# CompletePCBV5.net
KiCad netlist of a schematic drawn in EAGLE
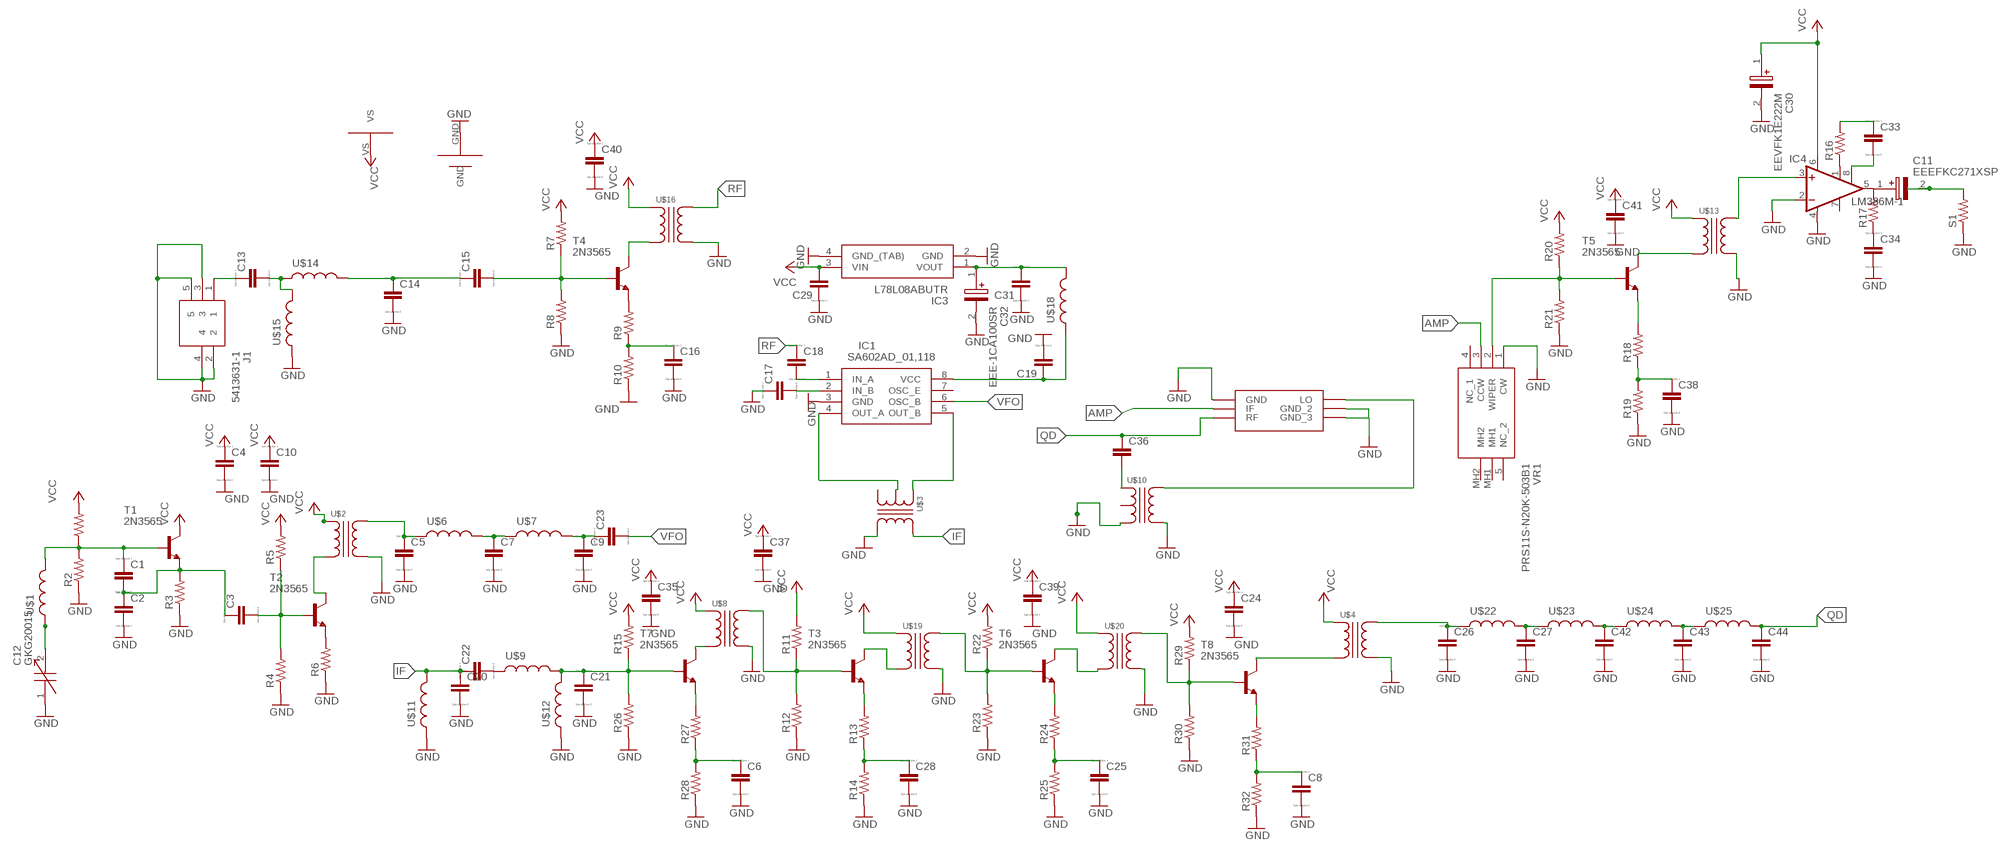
[diagram p0: schematic, sheet 1]

(export (version "E")
  (design (tool "Eeschema 10.0.6"))
  (components
    (comp (ref "C1") (value "C") (footprint "eagle-import:C0805") (libsource (lib "eagle-import") (part "C")))
    (comp (ref "C2") (value "C") (footprint "eagle-import:C0805") (libsource (lib "eagle-import") (part "C")))
    (comp (ref "C3") (value "C") (footprint "eagle-import:C0805") (libsource (lib "eagle-import") (part "C")))
    (comp (ref "C4") (value "C") (footprint "eagle-import:C0805") (libsource (lib "eagle-import") (part "C")))
    (comp (ref "C5") (value "C") (footprint "eagle-import:C0805") (libsource (lib "eagle-import") (part "C")))
    (comp (ref "C6") (value "C") (footprint "eagle-import:C0805") (libsource (lib "eagle-import") (part "C")))
    (comp (ref "C7") (value "C") (footprint "eagle-import:C0805") (libsource (lib "eagle-import") (part "C")))
    (comp (ref "C8") (value "C") (footprint "eagle-import:C0805") (libsource (lib "eagle-import") (part "C")))
    (comp (ref "C9") (value "C") (footprint "eagle-import:C0805") (libsource (lib "eagle-import") (part "C")))
    (comp (ref "C10")
      (value "C")
      (footprint "eagle-import:C0805")
      (libsource (lib "eagle-import") (part "C"))
    )
    (comp (ref "C11")
      (value "EEEFKC271XSP")
      (footprint "eagle-import:FKSV(D8)")
      (libsource (lib "eagle-import") (part "EEEFKC271XSP"))
    )
    (comp (ref "C12")
      (value "GKG20015")
      (footprint "eagle-import:GKG20015")
      (fields (field (name "MOUSER_PART_NUMBER") "659-GKG20015"))
      (libsource (lib "eagle-import") (part "GKG20015"))
    )
    (comp (ref "C13")
      (value "C")
      (footprint "eagle-import:C0805")
      (libsource (lib "eagle-import") (part "C"))
    )
    (comp (ref "C14")
      (value "C")
      (footprint "eagle-import:C0805")
      (libsource (lib "eagle-import") (part "C"))
    )
    (comp (ref "C15")
      (value "C")
      (footprint "eagle-import:C0805")
      (libsource (lib "eagle-import") (part "C"))
    )
    (comp (ref "C16")
      (value "C")
      (footprint "eagle-import:C0805")
      (libsource (lib "eagle-import") (part "C"))
    )
    (comp (ref "C17")
      (value "C")
      (footprint "eagle-import:C0805")
      (libsource (lib "eagle-import") (part "C"))
    )
    (comp (ref "C18")
      (value "C")
      (footprint "eagle-import:C0805")
      (libsource (lib "eagle-import") (part "C"))
    )
    (comp (ref "C19")
      (value "C")
      (footprint "eagle-import:C0805")
      (libsource (lib "eagle-import") (part "C"))
    )
    (comp (ref "C20")
      (value "C")
      (footprint "eagle-import:C0805")
      (libsource (lib "eagle-import") (part "C"))
    )
    (comp (ref "C21")
      (value "C")
      (footprint "eagle-import:C0805")
      (libsource (lib "eagle-import") (part "C"))
    )
    (comp (ref "C22")
      (value "C")
      (footprint "eagle-import:C0805")
      (libsource (lib "eagle-import") (part "C"))
    )
    (comp (ref "C23")
      (value "C")
      (footprint "eagle-import:C0805")
      (libsource (lib "eagle-import") (part "C"))
    )
    (comp (ref "C24")
      (value "C")
      (footprint "eagle-import:C0805")
      (libsource (lib "eagle-import") (part "C"))
    )
    (comp (ref "C25")
      (value "C")
      (footprint "eagle-import:C0805")
      (libsource (lib "eagle-import") (part "C"))
    )
    (comp (ref "C26")
      (value "C")
      (footprint "eagle-import:C0805")
      (libsource (lib "eagle-import") (part "C"))
    )
    (comp (ref "C27")
      (value "C")
      (footprint "eagle-import:C0805")
      (libsource (lib "eagle-import") (part "C"))
    )
    (comp (ref "C28")
      (value "C")
      (footprint "eagle-import:C0805")
      (libsource (lib "eagle-import") (part "C"))
    )
    (comp (ref "C29")
      (value "C")
      (footprint "eagle-import:C0805")
      (libsource (lib "eagle-import") (part "C"))
    )
    (comp (ref "C30")
      (value "EEVFK1E222M")
      (footprint "eagle-import:FKV(J16)")
      (libsource (lib "eagle-import") (part "EEVFK1E222M"))
    )
    (comp (ref "C31")
      (value "C")
      (footprint "eagle-import:C0805")
      (libsource (lib "eagle-import") (part "C"))
    )
    (comp (ref "C32")
      (value "EEE-1CA100SR")
      (footprint "eagle-import:SV(B)")
      (fields (field (name "MOUSER_PART_NUMBER") "667-EEE-1CA100SR"))
      (libsource (lib "eagle-import") (part "EEE-1CA100SR"))
    )
    (comp (ref "C33")
      (value "C")
      (footprint "eagle-import:C0805")
      (libsource (lib "eagle-import") (part "C"))
    )
    (comp (ref "C34")
      (value "CC1206")
      (footprint "eagle-import:C1206")
      (libsource (lib "eagle-import") (part "CC1206"))
    )
    (comp (ref "C35")
      (value "C")
      (footprint "eagle-import:C0805")
      (libsource (lib "eagle-import") (part "C"))
    )
    (comp (ref "C36")
      (value "C-EUC0805")
      (footprint "eagle-import:C0805")
      (libsource (lib "eagle-import") (part "C-EUC0805"))
    )
    (comp (ref "C37")
      (value "C")
      (footprint "eagle-import:C0805")
      (libsource (lib "eagle-import") (part "C"))
    )
    (comp (ref "C38")
      (value "C")
      (footprint "eagle-import:C0805")
      (libsource (lib "eagle-import") (part "C"))
    )
    (comp (ref "C39")
      (value "C")
      (footprint "eagle-import:C0805")
      (libsource (lib "eagle-import") (part "C"))
    )
    (comp (ref "C40")
      (value "C")
      (footprint "eagle-import:C0805")
      (libsource (lib "eagle-import") (part "C"))
    )
    (comp (ref "C41")
      (value "C")
      (footprint "eagle-import:C0805")
      (libsource (lib "eagle-import") (part "C"))
    )
    (comp (ref "C42")
      (value "C")
      (footprint "eagle-import:C0805")
      (libsource (lib "eagle-import") (part "C"))
    )
    (comp (ref "C43")
      (value "C")
      (footprint "eagle-import:C0805")
      (libsource (lib "eagle-import") (part "C"))
    )
    (comp (ref "C44")
      (value "C")
      (footprint "eagle-import:C0805")
      (libsource (lib "eagle-import") (part "C"))
    )
    (comp (ref "IC1")
      (value "SA602AD_01,118")
      (footprint "eagle-import:SOIC127P600X175-8N")
      (fields
        (field (name "MANUFACTURER_PART_NUMBER") "SA602AD/01,118")
        (field (name "MOUSER_PART_NUMBER") "771-SA602AD/01-T")
      )
      (libsource (lib "eagle-import") (part "SA602AD_01,118"))
    )
    (comp (ref "IC3")
      (value "L78L08ABUTR")
      (footprint "eagle-import:ST-SOT-89")
      (fields (field (name "MOUSER_PART_NUMBER") "511-L78L08ABU"))
      (libsource (lib "eagle-import") (part "L78L08ABUTR"))
    )
    (comp (ref "IC4")
      (value "LM386M-1")
      (footprint "eagle-import:SO08")
      (libsource (lib "eagle-import") (part "LM386?-M1"))
    )
    (comp (ref "J1")
      (value "5413631-1")
      (footprint "eagle-import:54136311")
      (fields (field (name "MOUSER_PART_NUMBER") "571-5413631-1"))
      (libsource (lib "eagle-import") (part "5413631-1"))
    )
    (comp (ref "R1")
      (value "R-US_R0805")
      (footprint "eagle-import:R0805")
      (libsource (lib "eagle-import") (part "resistor_348_R-US_R0805"))
    )
    (comp (ref "R2")
      (value "R-US_R0805")
      (footprint "eagle-import:R0805")
      (libsource (lib "eagle-import") (part "resistor_348_R-US_R0805"))
    )
    (comp (ref "R3")
      (value "R-US_R0805")
      (footprint "eagle-import:R0805")
      (libsource (lib "eagle-import") (part "resistor_348_R-US_R0805"))
    )
    (comp (ref "R4")
      (value "R-US_R0805")
      (footprint "eagle-import:R0805")
      (libsource (lib "eagle-import") (part "resistor_348_R-US_R0805"))
    )
    (comp (ref "R5")
      (value "R-US_R0805")
      (footprint "eagle-import:R0805")
      (libsource (lib "eagle-import") (part "resistor_348_R-US_R0805"))
    )
    (comp (ref "R6")
      (value "R-US_R0805")
      (footprint "eagle-import:R0805")
      (libsource (lib "eagle-import") (part "resistor_348_R-US_R0805"))
    )
    (comp (ref "R7")
      (value "R-US_R0805")
      (footprint "eagle-import:R0805")
      (libsource (lib "eagle-import") (part "resistor_348_R-US_R0805"))
    )
    (comp (ref "R8")
      (value "R-US_R0805")
      (footprint "eagle-import:R0805")
      (libsource (lib "eagle-import") (part "resistor_348_R-US_R0805"))
    )
    (comp (ref "R9")
      (value "R-US_R0805")
      (footprint "eagle-import:R0805")
      (libsource (lib "eagle-import") (part "resistor_348_R-US_R0805"))
    )
    (comp (ref "R10")
      (value "R-US_R0805")
      (footprint "eagle-import:R0805")
      (libsource (lib "eagle-import") (part "resistor_348_R-US_R0805"))
    )
    (comp (ref "R11")
      (value "R-US_R0805")
      (footprint "eagle-import:R0805")
      (libsource (lib "eagle-import") (part "resistor_348_R-US_R0805"))
    )
    (comp (ref "R12")
      (value "R-US_R0805")
      (footprint "eagle-import:R0805")
      (libsource (lib "eagle-import") (part "resistor_348_R-US_R0805"))
    )
    (comp (ref "R13")
      (value "R-US_R0805")
      (footprint "eagle-import:R0805")
      (libsource (lib "eagle-import") (part "resistor_348_R-US_R0805"))
    )
    (comp (ref "R14")
      (value "R-US_R0805")
      (footprint "eagle-import:R0805")
      (libsource (lib "eagle-import") (part "resistor_348_R-US_R0805"))
    )
    (comp (ref "R15")
      (value "R-US_R0805")
      (footprint "eagle-import:R0805")
      (libsource (lib "eagle-import") (part "resistor_348_R-US_R0805"))
    )
    (comp (ref "R16")
      (value "R-US_R0805")
      (footprint "eagle-import:R0805")
      (libsource (lib "eagle-import") (part "resistor_348_R-US_R0805"))
    )
    (comp (ref "R17")
      (value "R-US_R0805")
      (footprint "eagle-import:R0805")
      (libsource (lib "eagle-import") (part "resistor_348_R-US_R0805"))
    )
    (comp (ref "R18")
      (value "R-US_R0805")
      (footprint "eagle-import:R0805")
      (libsource (lib "eagle-import") (part "resistor_348_R-US_R0805"))
    )
    (comp (ref "R19")
      (value "R-US_R0805")
      (footprint "eagle-import:R0805")
      (libsource (lib "eagle-import") (part "resistor_348_R-US_R0805"))
    )
    (comp (ref "R20")
      (value "R-US_R0805")
      (footprint "eagle-import:R0805")
      (libsource (lib "eagle-import") (part "resistor_348_R-US_R0805"))
    )
    (comp (ref "R21")
      (value "R-US_R0805")
      (footprint "eagle-import:R0805")
      (libsource (lib "eagle-import") (part "resistor_348_R-US_R0805"))
    )
    (comp (ref "R22")
      (value "R-US_R0805")
      (footprint "eagle-import:R0805")
      (libsource (lib "eagle-import") (part "resistor_348_R-US_R0805"))
    )
    (comp (ref "R23")
      (value "R-US_R0805")
      (footprint "eagle-import:R0805")
      (libsource (lib "eagle-import") (part "resistor_348_R-US_R0805"))
    )
    (comp (ref "R24")
      (value "R-US_R0805")
      (footprint "eagle-import:R0805")
      (libsource (lib "eagle-import") (part "resistor_348_R-US_R0805"))
    )
    (comp (ref "R25")
      (value "R-US_R0805")
      (footprint "eagle-import:R0805")
      (libsource (lib "eagle-import") (part "resistor_348_R-US_R0805"))
    )
    (comp (ref "R26")
      (value "R-US_R0805")
      (footprint "eagle-import:R0805")
      (libsource (lib "eagle-import") (part "resistor_348_R-US_R0805"))
    )
    (comp (ref "R27")
      (value "R-US_R0805")
      (footprint "eagle-import:R0805")
      (libsource (lib "eagle-import") (part "resistor_348_R-US_R0805"))
    )
    (comp (ref "R28")
      (value "R-US_R0805")
      (footprint "eagle-import:R0805")
      (libsource (lib "eagle-import") (part "resistor_348_R-US_R0805"))
    )
    (comp (ref "R29")
      (value "R-US_R0805")
      (footprint "eagle-import:R0805")
      (libsource (lib "eagle-import") (part "resistor_348_R-US_R0805"))
    )
    (comp (ref "R30")
      (value "R-US_R0805")
      (footprint "eagle-import:R0805")
      (libsource (lib "eagle-import") (part "resistor_348_R-US_R0805"))
    )
    (comp (ref "R31")
      (value "R-US_R0805")
      (footprint "eagle-import:R0805")
      (libsource (lib "eagle-import") (part "resistor_348_R-US_R0805"))
    )
    (comp (ref "R32")
      (value "R-US_R0805")
      (footprint "eagle-import:R0805")
      (libsource (lib "eagle-import") (part "resistor_348_R-US_R0805"))
    )
    (comp (ref "S1")
      (value "R-US_0207/5V")
      (footprint "eagle-import:0207_5V")
      (libsource (lib "eagle-import") (part "R-US_0207/5V"))
    )
    (comp (ref "T1")
      (value "2N3565")
      (footprint "eagle-import:TO92")
      (libsource (lib "eagle-import") (part "2N3565"))
    )
    (comp (ref "T2")
      (value "2N3565")
      (footprint "eagle-import:TO92")
      (libsource (lib "eagle-import") (part "2N3565"))
    )
    (comp (ref "T3")
      (value "2N3565")
      (footprint "eagle-import:TO92")
      (libsource (lib "eagle-import") (part "2N3565"))
    )
    (comp (ref "T4")
      (value "2N3565")
      (footprint "eagle-import:TO92")
      (libsource (lib "eagle-import") (part "2N3565"))
    )
    (comp (ref "T5")
      (value "2N3565")
      (footprint "eagle-import:TO92")
      (libsource (lib "eagle-import") (part "2N3565"))
    )
    (comp (ref "T6")
      (value "2N3565")
      (footprint "eagle-import:TO92")
      (libsource (lib "eagle-import") (part "2N3565"))
    )
    (comp (ref "T7")
      (value "2N3565")
      (footprint "eagle-import:TO92")
      (libsource (lib "eagle-import") (part "2N3565"))
    )
    (comp (ref "T8")
      (value "2N3565")
      (footprint "eagle-import:TO92")
      (libsource (lib "eagle-import") (part "2N3565"))
    )
    (comp (ref "U$1")
      (value "WOUNDINDUCTOR")
      (footprint "eagle-import:WOUNDINDUCTOR")
      (libsource (lib "eagle-import") (part "WOUNDINDUCTOR"))
    )
    (comp (ref "U$2")
      (value "RFTRANSFORMER")
      (footprint "eagle-import:RFTRABSFORMER")
      (libsource (lib "eagle-import") (part "RFTRANSFORMER"))
    )
    (comp (ref "U$3")
      (value "42IF123")
      (footprint "eagle-import:42IF123")
      (libsource (lib "eagle-import") (part "42IF123"))
    )
    (comp (ref "U$4")
      (value "RFTRANSFORMER")
      (footprint "eagle-import:RFTRABSFORMER")
      (libsource (lib "eagle-import") (part "RFTRANSFORMER"))
    )
    (comp (ref "U$5")
      (value "ALLIGATORCLIPS")
      (footprint "eagle-import:ALLIGATORCONNECTOR")
      (libsource (lib "eagle-import") (part "ALLIGATORCLIPS"))
    )
    (comp (ref "U$6")
      (value "WOUNDINDUCTOR")
      (footprint "eagle-import:WOUNDINDUCTOR")
      (libsource (lib "eagle-import") (part "WOUNDINDUCTOR"))
    )
    (comp (ref "U$7")
      (value "WOUNDINDUCTOR")
      (footprint "eagle-import:WOUNDINDUCTOR")
      (libsource (lib "eagle-import") (part "WOUNDINDUCTOR"))
    )
    (comp (ref "U$8")
      (value "RFTRANSFORMER")
      (footprint "eagle-import:RFTRABSFORMER")
      (libsource (lib "eagle-import") (part "RFTRANSFORMER"))
    )
    (comp (ref "U$9")
      (value "WOUNDINDUCTOR")
      (footprint "eagle-import:WOUNDINDUCTOR")
      (libsource (lib "eagle-import") (part "WOUNDINDUCTOR"))
    )
    (comp (ref "U$10")
      (value "42IF123")
      (footprint "eagle-import:42IF123")
      (libsource (lib "eagle-import") (part "42IF123"))
    )
    (comp (ref "U$11")
      (value "WOUNDINDUCTOR")
      (footprint "eagle-import:WOUNDINDUCTOR")
      (libsource (lib "eagle-import") (part "WOUNDINDUCTOR"))
    )
    (comp (ref "U$12")
      (value "WOUNDINDUCTOR")
      (footprint "eagle-import:WOUNDINDUCTOR")
      (libsource (lib "eagle-import") (part "WOUNDINDUCTOR"))
    )
    (comp (ref "U$13")
      (value "RFTRANSFORMER")
      (footprint "eagle-import:RFTRABSFORMER")
      (libsource (lib "eagle-import") (part "RFTRANSFORMER"))
    )
    (comp (ref "U$14")
      (value "WOUNDINDUCTOR")
      (footprint "eagle-import:WOUNDINDUCTOR")
      (libsource (lib "eagle-import") (part "WOUNDINDUCTOR"))
    )
    (comp (ref "U$15")
      (value "WOUNDINDUCTOR")
      (footprint "eagle-import:WOUNDINDUCTOR")
      (libsource (lib "eagle-import") (part "WOUNDINDUCTOR"))
    )
    (comp (ref "U$16")
      (value "RFTRANSFORMER")
      (footprint "eagle-import:RFTRABSFORMER")
      (libsource (lib "eagle-import") (part "RFTRANSFORMER"))
    )
    (comp (ref "U$17")
      (value "ADE-1")
      (footprint "eagle-import:ADE-1")
      (libsource (lib "eagle-import") (part "ADE-1"))
    )
    (comp (ref "U$18")
      (value "WOUNDINDUCTOR")
      (footprint "eagle-import:WOUNDINDUCTOR")
      (libsource (lib "eagle-import") (part "WOUNDINDUCTOR"))
    )
    (comp (ref "U$19")
      (value "RFTRANSFORMER")
      (footprint "eagle-import:RFTRABSFORMER")
      (libsource (lib "eagle-import") (part "RFTRANSFORMER"))
    )
    (comp (ref "U$20")
      (value "RFTRANSFORMER")
      (footprint "eagle-import:RFTRABSFORMER")
      (libsource (lib "eagle-import") (part "RFTRANSFORMER"))
    )
    (comp (ref "U$22")
      (value "WOUNDINDUCTOR")
      (footprint "eagle-import:WOUNDINDUCTOR")
      (libsource (lib "eagle-import") (part "WOUNDINDUCTOR"))
    )
    (comp (ref "U$23")
      (value "WOUNDINDUCTOR")
      (footprint "eagle-import:WOUNDINDUCTOR")
      (libsource (lib "eagle-import") (part "WOUNDINDUCTOR"))
    )
    (comp (ref "U$24")
      (value "WOUNDINDUCTOR")
      (footprint "eagle-import:WOUNDINDUCTOR")
      (libsource (lib "eagle-import") (part "WOUNDINDUCTOR"))
    )
    (comp (ref "U$25")
      (value "WOUNDINDUCTOR")
      (footprint "eagle-import:WOUNDINDUCTOR")
      (libsource (lib "eagle-import") (part "WOUNDINDUCTOR"))
    )
    (comp (ref "VR1")
      (value "PRS11S-N20K-503B1")
      (footprint "eagle-import:PRS11SN20K503B1")
      (fields (field (name "MOUSER_PART_NUMBER") "652-PRS11SN20K503B1"))
      (libsource (lib "eagle-import") (part "PRS11S-N20K-503B1"))
    )
  )
  (nets
    (net (code "1") (name "AMP") (class "Default")
      (node (ref "U$17") (pin "IF") (pinfunction "IF_IF") (pintype "bidirectional"))
      (node (ref "VR1") (pin "3") (pinfunction "CCW_3") (pintype "bidirectional"))
    )
    (net (code "2") (name "GND") (class "Default")
      (node (ref "C10") (pin "2") (pinfunction "2_2") (pintype "passive"))
      (node (ref "C12") (pin "1") (pinfunction "1_1") (pintype "bidirectional"))
      (node (ref "C14") (pin "2") (pinfunction "2_2") (pintype "passive"))
      (node (ref "C16") (pin "2") (pinfunction "2_2") (pintype "passive"))
      (node (ref "C17") (pin "1") (pinfunction "1_1") (pintype "passive"))
      (node (ref "C19") (pin "2") (pinfunction "2_2") (pintype "passive"))
      (node (ref "C2") (pin "2") (pinfunction "2_2") (pintype "passive"))
      (node (ref "C20") (pin "2") (pinfunction "2_2") (pintype "passive"))
      (node (ref "C21") (pin "2") (pinfunction "2_2") (pintype "passive"))
      (node (ref "C24") (pin "2") (pinfunction "2_2") (pintype "passive"))
      (node (ref "C25") (pin "2") (pinfunction "2_2") (pintype "passive"))
      (node (ref "C26") (pin "2") (pinfunction "2_2") (pintype "passive"))
      (node (ref "C27") (pin "2") (pinfunction "2_2") (pintype "passive"))
      (node (ref "C28") (pin "2") (pinfunction "2_2") (pintype "passive"))
      (node (ref "C29") (pin "1") (pinfunction "1_1") (pintype "passive"))
      (node (ref "C30") (pin "2") (pinfunction "-_2") (pintype "bidirectional"))
      (node (ref "C31") (pin "1") (pinfunction "1_1") (pintype "passive"))
      (node (ref "C32") (pin "2") (pinfunction "-_2") (pintype "bidirectional"))
      (node (ref "C34") (pin "2") (pinfunction "2_2") (pintype "passive"))
      (node (ref "C35") (pin "2") (pinfunction "2_2") (pintype "passive"))
      (node (ref "C37") (pin "2") (pinfunction "2_2") (pintype "passive"))
      (node (ref "C38") (pin "2") (pinfunction "2_2") (pintype "passive"))
      (node (ref "C39") (pin "2") (pinfunction "2_2") (pintype "passive"))
      (node (ref "C4") (pin "2") (pinfunction "2_2") (pintype "passive"))
      (node (ref "C40") (pin "2") (pinfunction "2_2") (pintype "passive"))
      (node (ref "C41") (pin "2") (pinfunction "2_2") (pintype "passive"))
      (node (ref "C42") (pin "2") (pinfunction "2_2") (pintype "passive"))
      (node (ref "C43") (pin "2") (pinfunction "2_2") (pintype "passive"))
      (node (ref "C44") (pin "2") (pinfunction "2_2") (pintype "passive"))
      (node (ref "C5") (pin "2") (pinfunction "2_2") (pintype "passive"))
      (node (ref "C6") (pin "2") (pinfunction "2_2") (pintype "passive"))
      (node (ref "C7") (pin "2") (pinfunction "2_2") (pintype "passive"))
      (node (ref "C8") (pin "2") (pinfunction "2_2") (pintype "passive"))
      (node (ref "C9") (pin "2") (pinfunction "2_2") (pintype "passive"))
      (node (ref "IC1") (pin "3") (pinfunction "GND_3") (pintype "power_in"))
      (node (ref "IC3") (pin "2") (pinfunction "GND_2") (pintype "power_in"))
      (node (ref "IC3") (pin "4") (pinfunction "GND_(TAB)_4") (pintype "power_in"))
      (node (ref "IC4") (pin "2") (pinfunction "-IN_2") (pintype "input"))
      (node (ref "IC4") (pin "4") (pinfunction "GND_4") (pintype "power_in"))
      (node (ref "J1") (pin "2") (pinfunction "2_2") (pintype "bidirectional"))
      (node (ref "J1") (pin "3") (pinfunction "3_3") (pintype "bidirectional"))
      (node (ref "J1") (pin "4") (pinfunction "4_4") (pintype "bidirectional"))
      (node (ref "J1") (pin "5") (pinfunction "5_5") (pintype "bidirectional"))
      (node (ref "R10") (pin "1") (pinfunction "1_1") (pintype "passive"))
      (node (ref "R12") (pin "1") (pinfunction "1_1") (pintype "passive"))
      (node (ref "R14") (pin "1") (pinfunction "1_1") (pintype "passive"))
      (node (ref "R19") (pin "1") (pinfunction "1_1") (pintype "passive"))
      (node (ref "R2") (pin "1") (pinfunction "1_1") (pintype "passive"))
      (node (ref "R21") (pin "1") (pinfunction "1_1") (pintype "passive"))
      (node (ref "R23") (pin "1") (pinfunction "1_1") (pintype "passive"))
      (node (ref "R25") (pin "1") (pinfunction "1_1") (pintype "passive"))
      (node (ref "R26") (pin "1") (pinfunction "1_1") (pintype "passive"))
      (node (ref "R28") (pin "1") (pinfunction "1_1") (pintype "passive"))
      (node (ref "R3") (pin "1") (pinfunction "1_1") (pintype "passive"))
      (node (ref "R30") (pin "1") (pinfunction "1_1") (pintype "passive"))
      (node (ref "R32") (pin "1") (pinfunction "1_1") (pintype "passive"))
      (node (ref "R4") (pin "1") (pinfunction "1_1") (pintype "passive"))
      (node (ref "R6") (pin "1") (pinfunction "1_1") (pintype "passive"))
      (node (ref "R8") (pin "1") (pinfunction "1_1") (pintype "passive"))
      (node (ref "S1") (pin "1") (pinfunction "1_1") (pintype "passive"))
      (node (ref "U$10") (pin "P$3") (pinfunction "P$2_P$3") (pintype "bidirectional"))
      (node (ref "U$10") (pin "P$4") (pinfunction "P$3_P$4") (pintype "bidirectional"))
      (node (ref "U$11") (pin "1") (pinfunction "1_1") (pintype "bidirectional"))
      (node (ref "U$12") (pin "1") (pinfunction "1_1") (pintype "bidirectional"))
      (node (ref "U$13") (pin "P$4") (pinfunction "P$3_P$4") (pintype "bidirectional"))
      (node (ref "U$15") (pin "1") (pinfunction "1_1") (pintype "bidirectional"))
      (node (ref "U$16") (pin "P$4") (pinfunction "P$3_P$4") (pintype "bidirectional"))
      (node (ref "U$17") (pin "GND") (pinfunction "GND_GND") (pintype "bidirectional"))
      (node (ref "U$17") (pin "GND2") (pinfunction "GND_2_GND2") (pintype "bidirectional"))
      (node (ref "U$17") (pin "GND3") (pinfunction "GND_3_GND3") (pintype "bidirectional"))
      (node (ref "U$19") (pin "P$4") (pinfunction "P$3_P$4") (pintype "bidirectional"))
      (node (ref "U$2") (pin "P$4") (pinfunction "P$3_P$4") (pintype "bidirectional"))
      (node (ref "U$20") (pin "P$4") (pinfunction "P$3_P$4") (pintype "bidirectional"))
      (node (ref "U$3") (pin "P$4") (pinfunction "P$3_P$4") (pintype "bidirectional"))
      (node (ref "U$4") (pin "P$4") (pinfunction "P$3_P$4") (pintype "bidirectional"))
      (node (ref "U$5") (pin "GND") (pinfunction "GND_GND") (pintype "bidirectional"))
      (node (ref "U$8") (pin "P$4") (pinfunction "P$3_P$4") (pintype "bidirectional"))
      (node (ref "VR1") (pin "1") (pinfunction "CW_1") (pintype "bidirectional"))
    )
    (net (code "3") (name "IF") (class "Default")
      (node (ref "C20") (pin "1") (pinfunction "1_1") (pintype "passive"))
      (node (ref "C22") (pin "1") (pinfunction "1_1") (pintype "passive"))
      (node (ref "U$11") (pin "2") (pinfunction "2_2") (pintype "bidirectional"))
      (node (ref "U$3") (pin "P$5") (pinfunction "P$4_P$5") (pintype "bidirectional"))
    )
    (net (code "4") (name "Net-(C6-Pad1)") (class "Default")
      (node (ref "C6") (pin "1") (pinfunction "1_1") (pintype "passive"))
      (node (ref "R27") (pin "1") (pinfunction "1_1") (pintype "passive"))
      (node (ref "R28") (pin "2") (pinfunction "2_2") (pintype "passive"))
    )
    (net (code "5") (name "Net-(C7-Pad1)") (class "Default")
      (node (ref "C7") (pin "1") (pinfunction "1_1") (pintype "passive"))
      (node (ref "U$6") (pin "2") (pinfunction "2_2") (pintype "bidirectional"))
      (node (ref "U$7") (pin "1") (pinfunction "1_1") (pintype "bidirectional"))
    )
    (net (code "6") (name "Net-(C8-Pad1)") (class "Default")
      (node (ref "C8") (pin "1") (pinfunction "1_1") (pintype "passive"))
      (node (ref "R31") (pin "1") (pinfunction "1_1") (pintype "passive"))
      (node (ref "R32") (pin "2") (pinfunction "2_2") (pintype "passive"))
    )
    (net (code "7") (name "Net-(C11-+)") (class "Default")
      (node (ref "C11") (pin "1") (pinfunction "+_1") (pintype "bidirectional"))
      (node (ref "IC4") (pin "5") (pinfunction "OUT_5") (pintype "output"))
      (node (ref "R17") (pin "2") (pinfunction "2_2") (pintype "passive"))
    )
    (net (code "8") (name "Net-(C11--)") (class "Default")
      (node (ref "C11") (pin "2") (pinfunction "-_2") (pintype "bidirectional"))
      (node (ref "S1") (pin "2") (pinfunction "2_2") (pintype "passive"))
    )
    (net (code "9") (name "Net-(C12-Pad2)") (class "Default")
      (node (ref "C12") (pin "2") (pinfunction "2_2") (pintype "bidirectional"))
      (node (ref "U$1") (pin "1") (pinfunction "1_1") (pintype "bidirectional"))
    )
    (net (code "10") (name "Net-(C13-Pad1)") (class "Default")
      (node (ref "C13") (pin "1") (pinfunction "1_1") (pintype "passive"))
      (node (ref "J1") (pin "1") (pinfunction "1_1") (pintype "bidirectional"))
    )
    (net (code "11") (name "Net-(C13-Pad2)") (class "Default")
      (node (ref "C13") (pin "2") (pinfunction "2_2") (pintype "passive"))
      (node (ref "U$14") (pin "1") (pinfunction "1_1") (pintype "bidirectional"))
      (node (ref "U$15") (pin "2") (pinfunction "2_2") (pintype "bidirectional"))
    )
    (net (code "12") (name "Net-(C14-Pad1)") (class "Default")
      (node (ref "C14") (pin "1") (pinfunction "1_1") (pintype "passive"))
      (node (ref "C15") (pin "1") (pinfunction "1_1") (pintype "passive"))
      (node (ref "U$14") (pin "2") (pinfunction "2_2") (pintype "bidirectional"))
    )
    (net (code "13") (name "Net-(C16-Pad1)") (class "Default")
      (node (ref "C16") (pin "1") (pinfunction "1_1") (pintype "passive"))
      (node (ref "R10") (pin "2") (pinfunction "2_2") (pintype "passive"))
      (node (ref "R9") (pin "1") (pinfunction "1_1") (pintype "passive"))
    )
    (net (code "14") (name "Net-(C22-Pad2)") (class "Default")
      (node (ref "C22") (pin "2") (pinfunction "2_2") (pintype "passive"))
      (node (ref "U$9") (pin "1") (pinfunction "1_1") (pintype "bidirectional"))
    )
    (net (code "15") (name "Net-(C23-Pad1)") (class "Default")
      (node (ref "C23") (pin "1") (pinfunction "1_1") (pintype "passive"))
      (node (ref "C9") (pin "1") (pinfunction "1_1") (pintype "passive"))
      (node (ref "U$7") (pin "2") (pinfunction "2_2") (pintype "bidirectional"))
    )
    (net (code "16") (name "Net-(C25-Pad1)") (class "Default")
      (node (ref "C25") (pin "1") (pinfunction "1_1") (pintype "passive"))
      (node (ref "R24") (pin "1") (pinfunction "1_1") (pintype "passive"))
      (node (ref "R25") (pin "2") (pinfunction "2_2") (pintype "passive"))
    )
    (net (code "17") (name "Net-(C27-Pad1)") (class "Default")
      (node (ref "C27") (pin "1") (pinfunction "1_1") (pintype "passive"))
      (node (ref "U$22") (pin "2") (pinfunction "2_2") (pintype "bidirectional"))
      (node (ref "U$23") (pin "1") (pinfunction "1_1") (pintype "bidirectional"))
    )
    (net (code "18") (name "Net-(C28-Pad1)") (class "Default")
      (node (ref "C28") (pin "1") (pinfunction "1_1") (pintype "passive"))
      (node (ref "R13") (pin "1") (pinfunction "1_1") (pintype "passive"))
      (node (ref "R14") (pin "2") (pinfunction "2_2") (pintype "passive"))
    )
    (net (code "19") (name "Net-(C32-+)") (class "Default")
      (node (ref "C31") (pin "2") (pinfunction "2_2") (pintype "passive"))
      (node (ref "C32") (pin "1") (pinfunction "+_1") (pintype "bidirectional"))
      (node (ref "IC3") (pin "1") (pinfunction "VOUT_1") (pintype "output"))
      (node (ref "U$18") (pin "2") (pinfunction "2_2") (pintype "bidirectional"))
    )
    (net (code "20") (name "Net-(C33-Pad1)") (class "Default")
      (node (ref "C33") (pin "1") (pinfunction "1_1") (pintype "passive"))
      (node (ref "R16") (pin "2") (pinfunction "2_2") (pintype "passive"))
    )
    (net (code "21") (name "Net-(C33-Pad2)") (class "Default")
      (node (ref "C33") (pin "2") (pinfunction "2_2") (pintype "passive"))
      (node (ref "IC4") (pin "8") (pinfunction "GAIN_8") (pintype "passive"))
    )
    (net (code "22") (name "Net-(C34-Pad1)") (class "Default")
      (node (ref "C34") (pin "1") (pinfunction "1_1") (pintype "passive"))
      (node (ref "R17") (pin "1") (pinfunction "1_1") (pintype "passive"))
    )
    (net (code "23") (name "Net-(C38-Pad1)") (class "Default")
      (node (ref "C38") (pin "1") (pinfunction "1_1") (pintype "passive"))
      (node (ref "R18") (pin "1") (pinfunction "1_1") (pintype "passive"))
      (node (ref "R19") (pin "2") (pinfunction "2_2") (pintype "passive"))
    )
    (net (code "24") (name "Net-(C42-Pad1)") (class "Default")
      (node (ref "C42") (pin "1") (pinfunction "1_1") (pintype "passive"))
      (node (ref "U$23") (pin "2") (pinfunction "2_2") (pintype "bidirectional"))
      (node (ref "U$24") (pin "1") (pinfunction "1_1") (pintype "bidirectional"))
    )
    (net (code "25") (name "Net-(C43-Pad1)") (class "Default")
      (node (ref "C43") (pin "1") (pinfunction "1_1") (pintype "passive"))
      (node (ref "U$24") (pin "2") (pinfunction "2_2") (pintype "bidirectional"))
      (node (ref "U$25") (pin "1") (pinfunction "1_1") (pintype "bidirectional"))
    )
    (net (code "26") (name "Net-(IC1-IN_A)") (class "Default")
      (node (ref "C18") (pin "2") (pinfunction "2_2") (pintype "passive"))
      (node (ref "IC1") (pin "1") (pinfunction "IN_A_1") (pintype "input"))
    )
    (net (code "27") (name "Net-(IC1-IN_B)") (class "Default")
      (node (ref "C17") (pin "2") (pinfunction "2_2") (pintype "passive"))
      (node (ref "IC1") (pin "2") (pinfunction "IN_B_2") (pintype "input"))
    )
    (net (code "28") (name "Net-(IC1-OUT_A)") (class "Default")
      (node (ref "IC1") (pin "4") (pinfunction "OUT_A_4") (pintype "output"))
      (node (ref "U$3") (pin "P$1") (pinfunction "P$5_P$1") (pintype "bidirectional"))
    )
    (net (code "29") (name "Net-(IC1-OUT_B)") (class "Default")
      (node (ref "IC1") (pin "5") (pinfunction "OUT_B_5") (pintype "output"))
      (node (ref "U$3") (pin "P$2") (pinfunction "P$1_P$2") (pintype "bidirectional"))
    )
    (net (code "30") (name "Net-(IC1-VCC)") (class "Default")
      (node (ref "C19") (pin "1") (pinfunction "1_1") (pintype "passive"))
      (node (ref "IC1") (pin "8") (pinfunction "VCC_8") (pintype "power_in"))
      (node (ref "U$18") (pin "1") (pinfunction "1_1") (pintype "bidirectional"))
    )
    (net (code "31") (name "Net-(IC4-+IN)") (class "Default")
      (node (ref "IC4") (pin "3") (pinfunction "+IN_3") (pintype "input"))
      (node (ref "U$13") (pin "P$3") (pinfunction "P$4_P$3") (pintype "bidirectional"))
    )
    (net (code "32") (name "Net-(IC4-GAIN-Pad1)") (class "Default")
      (node (ref "IC4") (pin "1") (pinfunction "GAIN_1") (pintype "passive"))
      (node (ref "R16") (pin "1") (pinfunction "1_1") (pintype "passive"))
    )
    (net (code "33") (name "Net-(T1-B)") (class "Default")
      (node (ref "C1") (pin "1") (pinfunction "1_1") (pintype "passive"))
      (node (ref "R1") (pin "1") (pinfunction "1_1") (pintype "passive"))
      (node (ref "R2") (pin "2") (pinfunction "2_2") (pintype "passive"))
      (node (ref "T1") (pin "2") (pinfunction "B_2") (pintype "passive"))
      (node (ref "U$1") (pin "2") (pinfunction "2_2") (pintype "bidirectional"))
    )
    (net (code "34") (name "Net-(T1-E)") (class "Default")
      (node (ref "C1") (pin "2") (pinfunction "2_2") (pintype "passive"))
      (node (ref "C2") (pin "1") (pinfunction "1_1") (pintype "passive"))
      (node (ref "C3") (pin "1") (pinfunction "1_1") (pintype "passive"))
      (node (ref "R3") (pin "2") (pinfunction "2_2") (pintype "passive"))
      (node (ref "T1") (pin "3") (pinfunction "E_3") (pintype "passive"))
    )
    (net (code "35") (name "Net-(T2-B)") (class "Default")
      (node (ref "C3") (pin "2") (pinfunction "2_2") (pintype "passive"))
      (node (ref "R4") (pin "2") (pinfunction "2_2") (pintype "passive"))
      (node (ref "R5") (pin "1") (pinfunction "1_1") (pintype "passive"))
      (node (ref "T2") (pin "2") (pinfunction "B_2") (pintype "passive"))
    )
    (net (code "36") (name "Net-(T2-C)") (class "Default")
      (node (ref "T2") (pin "1") (pinfunction "C_1") (pintype "passive"))
      (node (ref "U$2") (pin "P$1") (pinfunction "P$2_P$1") (pintype "bidirectional"))
    )
    (net (code "37") (name "Net-(T2-E)") (class "Default")
      (node (ref "R6") (pin "2") (pinfunction "2_2") (pintype "passive"))
      (node (ref "T2") (pin "3") (pinfunction "E_3") (pintype "passive"))
    )
    (net (code "38") (name "Net-(T3-B)") (class "Default")
      (node (ref "R11") (pin "1") (pinfunction "1_1") (pintype "passive"))
      (node (ref "R12") (pin "2") (pinfunction "2_2") (pintype "passive"))
      (node (ref "T3") (pin "2") (pinfunction "B_2") (pintype "passive"))
      (node (ref "U$8") (pin "P$3") (pinfunction "P$4_P$3") (pintype "bidirectional"))
    )
    (net (code "39") (name "Net-(T3-C)") (class "Default")
      (node (ref "T3") (pin "1") (pinfunction "C_1") (pintype "passive"))
      (node (ref "U$19") (pin "P$1") (pinfunction "P$2_P$1") (pintype "bidirectional"))
    )
    (net (code "40") (name "Net-(T3-E)") (class "Default")
      (node (ref "R13") (pin "2") (pinfunction "2_2") (pintype "passive"))
      (node (ref "T3") (pin "3") (pinfunction "E_3") (pintype "passive"))
    )
    (net (code "41") (name "Net-(T4-B)") (class "Default")
      (node (ref "C15") (pin "2") (pinfunction "2_2") (pintype "passive"))
      (node (ref "R7") (pin "1") (pinfunction "1_1") (pintype "passive"))
      (node (ref "R8") (pin "2") (pinfunction "2_2") (pintype "passive"))
      (node (ref "T4") (pin "2") (pinfunction "B_2") (pintype "passive"))
    )
    (net (code "42") (name "Net-(T4-C)") (class "Default")
      (node (ref "T4") (pin "1") (pinfunction "C_1") (pintype "passive"))
      (node (ref "U$16") (pin "P$1") (pinfunction "P$2_P$1") (pintype "bidirectional"))
    )
    (net (code "43") (name "Net-(T4-E)") (class "Default")
      (node (ref "R9") (pin "2") (pinfunction "2_2") (pintype "passive"))
      (node (ref "T4") (pin "3") (pinfunction "E_3") (pintype "passive"))
    )
    (net (code "44") (name "Net-(T5-B)") (class "Default")
      (node (ref "R20") (pin "1") (pinfunction "1_1") (pintype "passive"))
      (node (ref "R21") (pin "2") (pinfunction "2_2") (pintype "passive"))
      (node (ref "T5") (pin "2") (pinfunction "B_2") (pintype "passive"))
      (node (ref "VR1") (pin "2") (pinfunction "WIPER_2") (pintype "bidirectional"))
    )
    (net (code "45") (name "Net-(T5-C)") (class "Default")
      (node (ref "T5") (pin "1") (pinfunction "C_1") (pintype "passive"))
      (node (ref "U$13") (pin "P$1") (pinfunction "P$2_P$1") (pintype "bidirectional"))
    )
    (net (code "46") (name "Net-(T5-E)") (class "Default")
      (node (ref "R18") (pin "2") (pinfunction "2_2") (pintype "passive"))
      (node (ref "T5") (pin "3") (pinfunction "E_3") (pintype "passive"))
    )
    (net (code "47") (name "Net-(T6-B)") (class "Default")
      (node (ref "R22") (pin "1") (pinfunction "1_1") (pintype "passive"))
      (node (ref "R23") (pin "2") (pinfunction "2_2") (pintype "passive"))
      (node (ref "T6") (pin "2") (pinfunction "B_2") (pintype "passive"))
      (node (ref "U$19") (pin "P$3") (pinfunction "P$4_P$3") (pintype "bidirectional"))
    )
    (net (code "48") (name "Net-(T6-C)") (class "Default")
      (node (ref "T6") (pin "1") (pinfunction "C_1") (pintype "passive"))
      (node (ref "U$20") (pin "P$1") (pinfunction "P$2_P$1") (pintype "bidirectional"))
    )
    (net (code "49") (name "Net-(T6-E)") (class "Default")
      (node (ref "R24") (pin "2") (pinfunction "2_2") (pintype "passive"))
      (node (ref "T6") (pin "3") (pinfunction "E_3") (pintype "passive"))
    )
    (net (code "50") (name "Net-(T7-B)") (class "Default")
      (node (ref "C21") (pin "1") (pinfunction "1_1") (pintype "passive"))
      (node (ref "R15") (pin "1") (pinfunction "1_1") (pintype "passive"))
      (node (ref "R26") (pin "2") (pinfunction "2_2") (pintype "passive"))
      (node (ref "T7") (pin "2") (pinfunction "B_2") (pintype "passive"))
      (node (ref "U$12") (pin "2") (pinfunction "2_2") (pintype "bidirectional"))
      (node (ref "U$9") (pin "2") (pinfunction "2_2") (pintype "bidirectional"))
    )
    (net (code "51") (name "Net-(T7-C)") (class "Default")
      (node (ref "T7") (pin "1") (pinfunction "C_1") (pintype "passive"))
      (node (ref "U$8") (pin "P$1") (pinfunction "P$2_P$1") (pintype "bidirectional"))
    )
    (net (code "52") (name "Net-(T7-E)") (class "Default")
      (node (ref "R27") (pin "2") (pinfunction "2_2") (pintype "passive"))
      (node (ref "T7") (pin "3") (pinfunction "E_3") (pintype "passive"))
    )
    (net (code "53") (name "Net-(T8-B)") (class "Default")
      (node (ref "R29") (pin "1") (pinfunction "1_1") (pintype "passive"))
      (node (ref "R30") (pin "2") (pinfunction "2_2") (pintype "passive"))
      (node (ref "T8") (pin "2") (pinfunction "B_2") (pintype "passive"))
      (node (ref "U$20") (pin "P$3") (pinfunction "P$4_P$3") (pintype "bidirectional"))
    )
    (net (code "54") (name "Net-(T8-C)") (class "Default")
      (node (ref "T8") (pin "1") (pinfunction "C_1") (pintype "passive"))
      (node (ref "U$4") (pin "P$1") (pinfunction "P$2_P$1") (pintype "bidirectional"))
    )
    (net (code "55") (name "Net-(T8-E)") (class "Default")
      (node (ref "R31") (pin "2") (pinfunction "2_2") (pintype "passive"))
      (node (ref "T8") (pin "3") (pinfunction "E_3") (pintype "passive"))
    )
    (net (code "56") (name "Net-(U$2-P$4)") (class "Default")
      (node (ref "C5") (pin "1") (pinfunction "1_1") (pintype "passive"))
      (node (ref "U$2") (pin "P$3") (pinfunction "P$4_P$3") (pintype "bidirectional"))
      (node (ref "U$6") (pin "1") (pinfunction "1_1") (pintype "bidirectional"))
    )
    (net (code "57") (name "Net-(U$4-P$4)") (class "Default")
      (node (ref "C26") (pin "1") (pinfunction "1_1") (pintype "passive"))
      (node (ref "U$22") (pin "1") (pinfunction "1_1") (pintype "bidirectional"))
      (node (ref "U$4") (pin "P$3") (pinfunction "P$4_P$3") (pintype "bidirectional"))
    )
    (net (code "58") (name "Net-(U$10-P$1)") (class "Default")
      (node (ref "C36") (pin "2") (pinfunction "2_2") (pintype "passive"))
      (node (ref "U$10") (pin "P$2") (pinfunction "P$1_P$2") (pintype "bidirectional"))
    )
    (net (code "59") (name "Net-(U$10-P$4)") (class "Default")
      (node (ref "U$10") (pin "P$5") (pinfunction "P$4_P$5") (pintype "bidirectional"))
      (node (ref "U$17") (pin "LO") (pinfunction "LO_LO") (pintype "bidirectional"))
    )
    (net (code "60") (name "QD") (class "Default")
      (node (ref "C36") (pin "1") (pinfunction "1_1") (pintype "passive"))
      (node (ref "C44") (pin "1") (pinfunction "1_1") (pintype "passive"))
      (node (ref "U$17") (pin "RF") (pinfunction "RF_RF") (pintype "bidirectional"))
      (node (ref "U$25") (pin "2") (pinfunction "2_2") (pintype "bidirectional"))
    )
    (net (code "61") (name "RF") (class "Default")
      (node (ref "C18") (pin "1") (pinfunction "1_1") (pintype "passive"))
      (node (ref "U$16") (pin "P$3") (pinfunction "P$4_P$3") (pintype "bidirectional"))
    )
    (net (code "62") (name "VCC") (class "Default")
      (node (ref "C10") (pin "1") (pinfunction "1_1") (pintype "passive"))
      (node (ref "C24") (pin "1") (pinfunction "1_1") (pintype "passive"))
      (node (ref "C29") (pin "2") (pinfunction "2_2") (pintype "passive"))
      (node (ref "C30") (pin "1") (pinfunction "+_1") (pintype "bidirectional"))
      (node (ref "C35") (pin "1") (pinfunction "1_1") (pintype "passive"))
      (node (ref "C37") (pin "1") (pinfunction "1_1") (pintype "passive"))
      (node (ref "C39") (pin "1") (pinfunction "1_1") (pintype "passive"))
      (node (ref "C4") (pin "1") (pinfunction "1_1") (pintype "passive"))
      (node (ref "C40") (pin "1") (pinfunction "1_1") (pintype "passive"))
      (node (ref "C41") (pin "1") (pinfunction "1_1") (pintype "passive"))
      (node (ref "IC3") (pin "3") (pinfunction "VIN_3") (pintype "input"))
      (node (ref "IC4") (pin "6") (pinfunction "VS_6") (pintype "power_in"))
      (node (ref "R1") (pin "2") (pinfunction "2_2") (pintype "passive"))
      (node (ref "R11") (pin "2") (pinfunction "2_2") (pintype "passive"))
      (node (ref "R15") (pin "2") (pinfunction "2_2") (pintype "passive"))
      (node (ref "R20") (pin "2") (pinfunction "2_2") (pintype "passive"))
      (node (ref "R22") (pin "2") (pinfunction "2_2") (pintype "passive"))
      (node (ref "R29") (pin "2") (pinfunction "2_2") (pintype "passive"))
      (node (ref "R5") (pin "2") (pinfunction "2_2") (pintype "passive"))
      (node (ref "R7") (pin "2") (pinfunction "2_2") (pintype "passive"))
      (node (ref "T1") (pin "1") (pinfunction "C_1") (pintype "passive"))
      (node (ref "U$13") (pin "P$2") (pinfunction "P$1_P$2") (pintype "bidirectional"))
      (node (ref "U$16") (pin "P$2") (pinfunction "P$1_P$2") (pintype "bidirectional"))
      (node (ref "U$19") (pin "P$2") (pinfunction "P$1_P$2") (pintype "bidirectional"))
      (node (ref "U$2") (pin "P$2") (pinfunction "P$1_P$2") (pintype "bidirectional"))
      (node (ref "U$20") (pin "P$2") (pinfunction "P$1_P$2") (pintype "bidirectional"))
      (node (ref "U$4") (pin "P$2") (pinfunction "P$1_P$2") (pintype "bidirectional"))
      (node (ref "U$5") (pin "VS") (pinfunction "VS_VS") (pintype "bidirectional"))
      (node (ref "U$8") (pin "P$2") (pinfunction "P$1_P$2") (pintype "bidirectional"))
    )
    (net (code "63") (name "VFO") (class "Default")
      (node (ref "C23") (pin "2") (pinfunction "2_2") (pintype "passive"))
      (node (ref "IC1") (pin "6") (pinfunction "OSC_B_6") (pintype "bidirectional"))
    )
    (net (code "64") (name "unconnected-(IC1-OSC_E-Pad7)") (class "Default")
      (node (ref "IC1") (pin "7") (pinfunction "OSC_E_7") (pintype "bidirectional"))
    )
    (net (code "65") (name "unconnected-(IC4-BYPASS-Pad7)") (class "Default")
      (node (ref "IC4") (pin "7") (pinfunction "BYPASS_7") (pintype "passive"))
    )
    (net (code "66") (name "unconnected-(U$3-P$2-PadP$3)") (class "Default")
      (node (ref "U$3") (pin "P$3") (pinfunction "P$2_P$3") (pintype "bidirectional"))
    )
    (net (code "67") (name "unconnected-(U$10-P$5-PadP$1)") (class "Default")
      (node (ref "U$10") (pin "P$1") (pinfunction "P$5_P$1") (pintype "bidirectional"))
    )
    (net (code "68") (name "unconnected-(VR1-NC_1-Pad4)") (class "Default")
      (node (ref "VR1") (pin "4") (pinfunction "NC_1_4") (pintype "bidirectional"))
    )
    (net (code "69") (name "unconnected-(VR1-NC_2-Pad5)") (class "Default")
      (node (ref "VR1") (pin "5") (pinfunction "NC_2_5") (pintype "bidirectional"))
    )
    (net (code "70") (name "unconnected-(VR1-PadMH1)") (class "Default")
      (node (ref "VR1") (pin "MH1") (pinfunction "MH1_MH1") (pintype "bidirectional"))
    )
    (net (code "71") (name "unconnected-(VR1-PadMH2)") (class "Default")
      (node (ref "VR1") (pin "MH2") (pinfunction "MH2_MH2") (pintype "bidirectional"))
    )
  )
)
